# Power_Management.net
KiCad netlist of a schematic drawn in Altium Designer
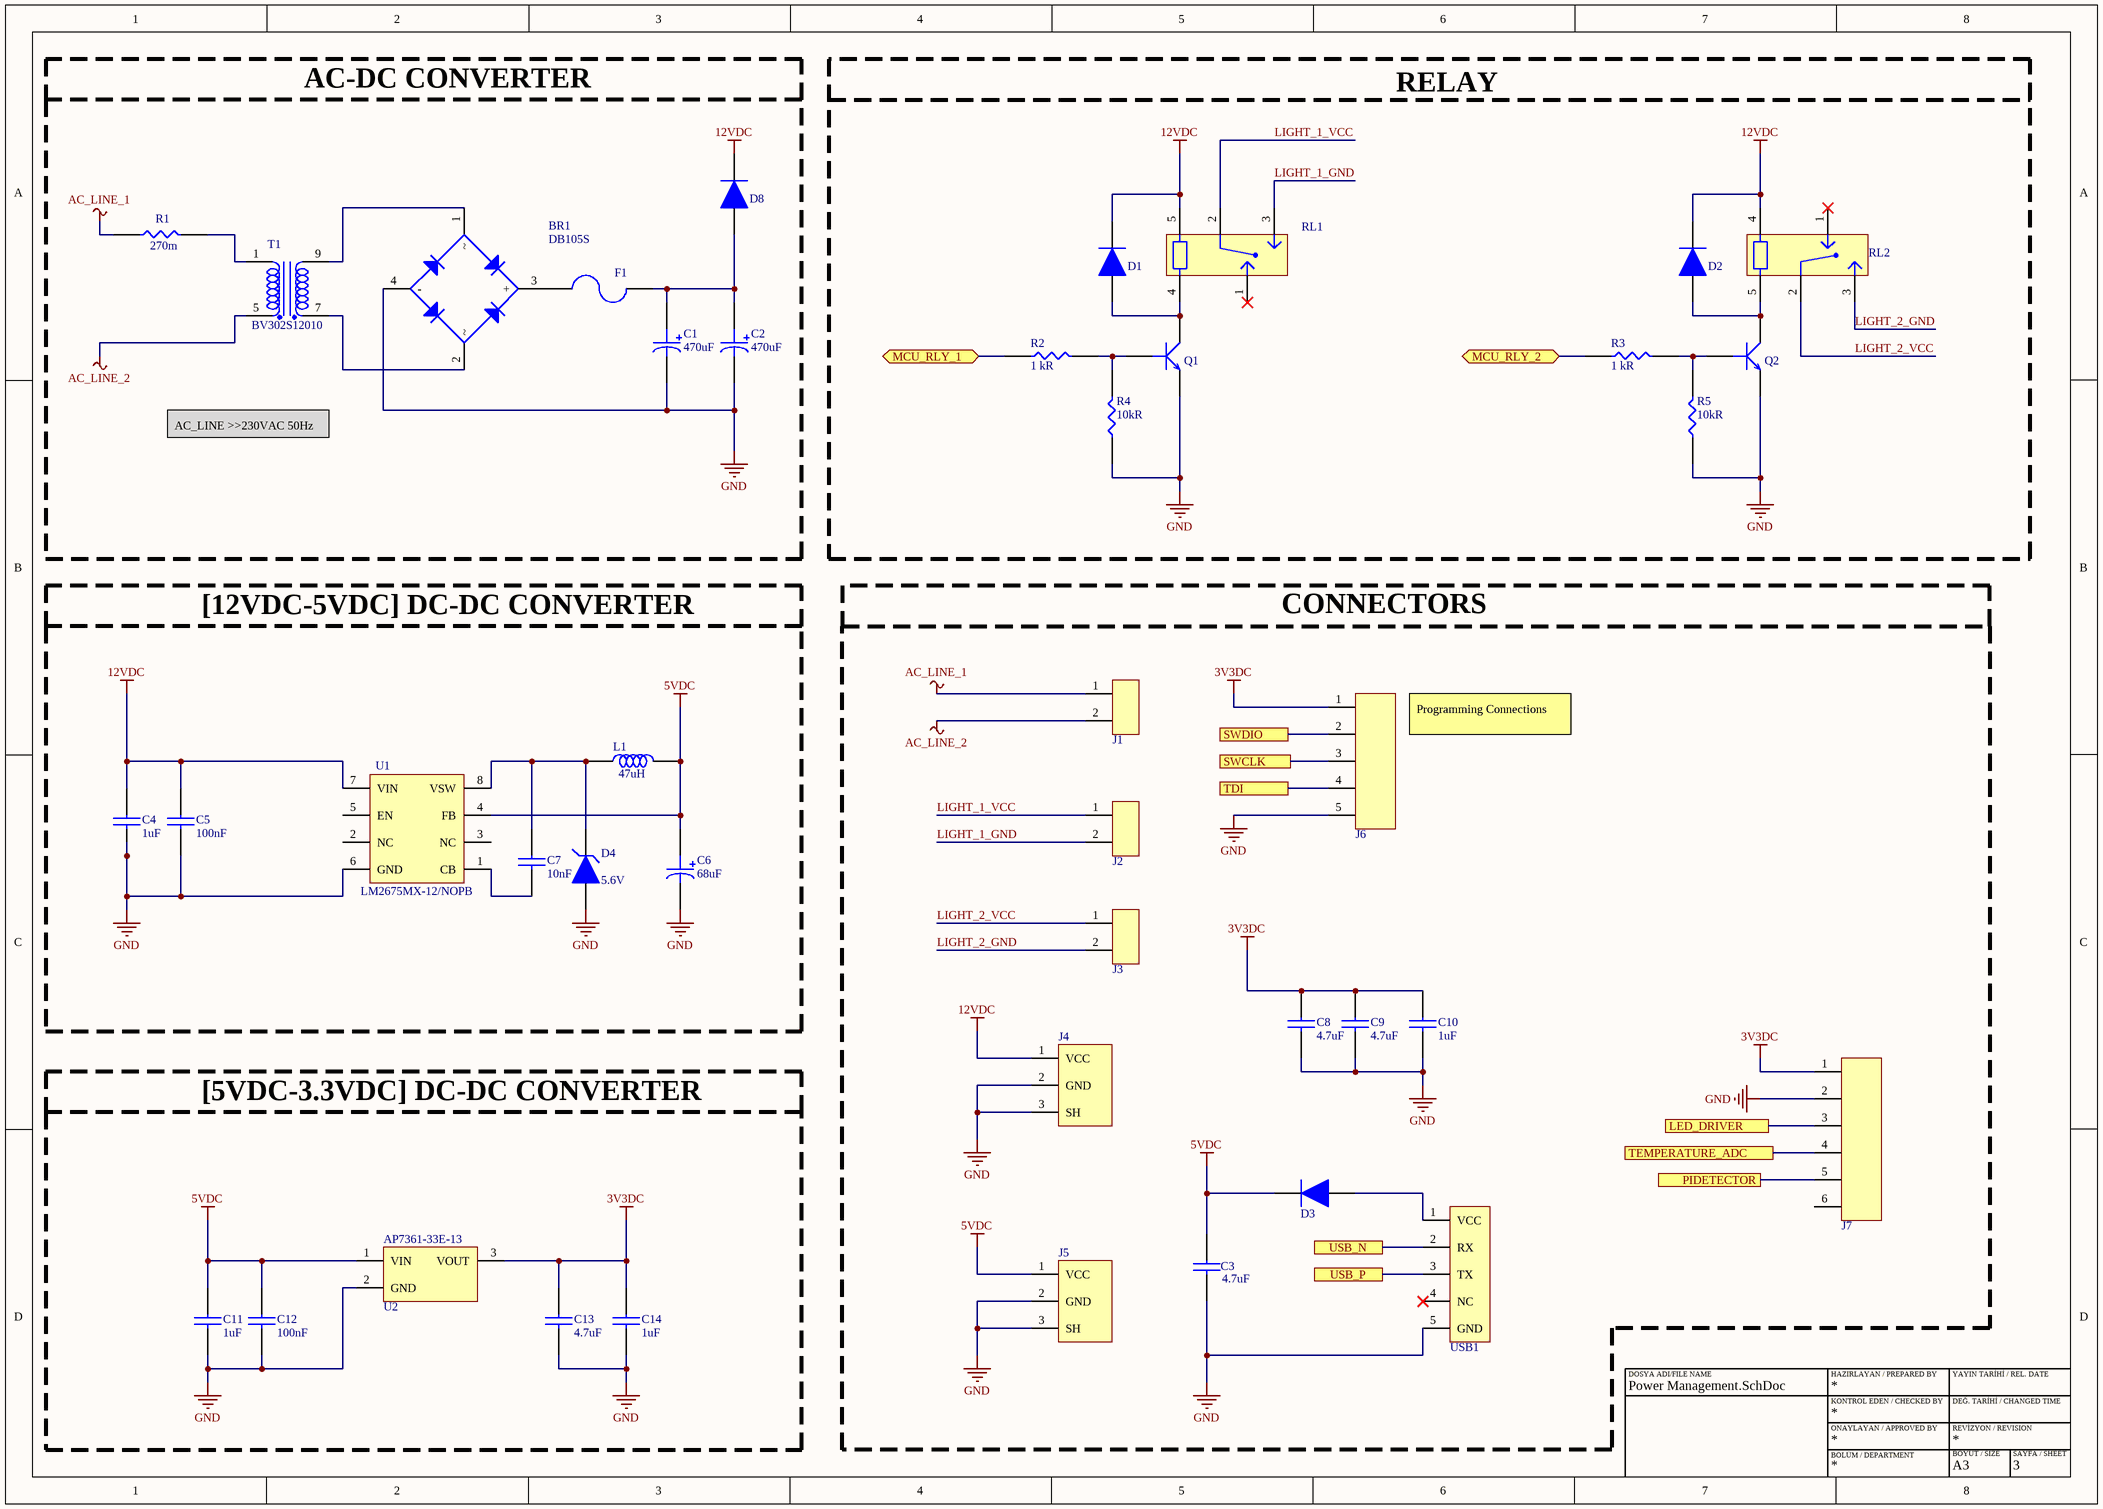
[diagram p0: Power Management.SchDoc]

(export (version "E")
  (design (tool "Eeschema 10.0.6"))
  (components
    (comp (ref "BR1")
      (value "DB105S")
      (footprint "DB105S")
      (description "Rectifier Bridge Diode Single 600V 1A 4-Pin SMD")
      (fields (field (name "MANUFACTURER") "Multicomp"))
      (libsource (lib "Integrated_Library1") (part "DB105S"))
    )
    (comp (ref "C1")
      (value "470uF")
      (footprint "CAP_RADIAL_D10_P5")
      (description "CAP ALU ELEC 470uF 50V 20%")
      (fields
        (field (name "MANUFACTURER") "KEMET")
        (field (name "MANUFACTURER PART NUMBER") "ESH477M050AH4AA")
        (field (name "DESIGNED BY") "MCP")
      )
      (libsource (lib "Integrated_Library1") (part "CAP ALU ELEC 470uF 50V"))
    )
    (comp (ref "C2")
      (value "470uF")
      (footprint "CAP_RADIAL_D10_P5")
      (description "CAP ALU ELEC 470uF 50V 20%")
      (fields
        (field (name "MANUFACTURER") "KEMET")
        (field (name "MANUFACTURER PART NUMBER") "ESH477M050AH4AA")
        (field (name "DESIGNED BY") "MCP")
      )
      (libsource (lib "Integrated_Library1") (part "CAP ALU ELEC 470uF 50V"))
    )
    (comp (ref "C3")
      (value "4.7uF")
      (footprint "CAP_0805")
      (description "CAP CER 4.7uF 10% 0805")
      (fields
        (field (name "MANUFACTURER") "Samsung")
        (field (name "MANUFACTURER PART NUMBER") "CL21A475KAQNNNE")
        (field (name "DESIGNED BY") "MCP")
      )
      (libsource (lib "Integrated_Library1") (part "CAP CER 4.7uF 0805"))
    )
    (comp (ref "C4")
      (value "1uF")
      (footprint "CAP_0805")
      (description "CAP CER 1uF 10% 0805")
      (fields
        (field (name "MANUFACTURER") "Samsung")
        (field (name "MANUFACTURER PART NUMBER") "CL21B105KBFNNNE")
        (field (name "DESIGNED BY") "MCP")
      )
      (libsource (lib "Integrated_Library1") (part "CAP CER 1uF 0805"))
    )
    (comp (ref "C5")
      (value "100nF")
      (footprint "CAP_0805")
      (description "CAP CER 100nF 10% 0805")
      (fields
        (field (name "MANUFACTURER") "Samsung")
        (field (name "MANUFACTURER PART NUMBER") "CL21B104KBCNNNC")
        (field (name "DESIGNED BY") "MCP")
      )
      (libsource (lib "Integrated_Library1") (part "CAP CER 100nF 0805"))
    )
    (comp (ref "C6")
      (value "68uF")
      (footprint "CAP_EEVSERIES")
      (description "CAP ALU 68uF 20%")
      (fields
        (field (name "MANUFACTURER") "KEMET")
        (field (name "MANUFACTURER PART NUMBER") "EEV686M035A9HAA")
        (field (name "DESIGNED BY") "MCP")
      )
      (libsource (lib "Integrated_Library1") (part "CAP ALU 68uF"))
    )
    (comp (ref "C7")
      (value "10nF")
      (footprint "CAP_0603")
      (description "CAP CER 10nF 10% 0603")
      (fields
        (field (name "MANUFACTURER") "Walsin Technologies")
        (field (name "MANUFACTURER PART NUMBER") "0603B103K160CT")
        (field (name "DESIGNED BY") "MCP")
      )
      (libsource (lib "Integrated_Library1") (part "CAP CER 10nF 0603"))
    )
    (comp (ref "C8")
      (value "4.7uF")
      (footprint "CAP_0805")
      (description "CAP CER 4.7uF 10% 0805")
      (fields
        (field (name "MANUFACTURER") "Samsung")
        (field (name "MANUFACTURER PART NUMBER") "CL21A475KAQNNNE")
        (field (name "DESIGNED BY") "MCP")
      )
      (libsource (lib "Integrated_Library1") (part "CAP CER 4.7uF 0805"))
    )
    (comp (ref "C9")
      (value "4.7uF")
      (footprint "CAP_0805")
      (description "CAP CER 4.7uF 10% 0805")
      (fields
        (field (name "MANUFACTURER") "Samsung")
        (field (name "MANUFACTURER PART NUMBER") "CL21A475KAQNNNE")
        (field (name "DESIGNED BY") "MCP")
      )
      (libsource (lib "Integrated_Library1") (part "CAP CER 4.7uF 0805"))
    )
    (comp (ref "C10")
      (value "1uF")
      (footprint "CAP_0805")
      (description "CAP CER 1uF 10% 0805")
      (fields
        (field (name "MANUFACTURER") "Samsung")
        (field (name "MANUFACTURER PART NUMBER") "CL21B105KBFNNNE")
        (field (name "DESIGNED BY") "MCP")
      )
      (libsource (lib "Integrated_Library1") (part "CAP CER 1uF 0805"))
    )
    (comp (ref "C11")
      (value "1uF")
      (footprint "CAP_0805")
      (description "CAP CER 1uF 10% 0805")
      (fields
        (field (name "MANUFACTURER") "Samsung")
        (field (name "MANUFACTURER PART NUMBER") "CL21B105KBFNNNE")
        (field (name "DESIGNED BY") "MCP")
      )
      (libsource (lib "Integrated_Library1") (part "CAP CER 1uF 0805"))
    )
    (comp (ref "C12")
      (value "100nF")
      (footprint "CAP_0603")
      (description "CAP CER 100nF 10% 0603")
      (fields
        (field (name "MANUFACTURER") "KEMET")
        (field (name "MANUFACTURER PART NUMBER") "C0603C104K5RACTU")
        (field (name "DESIGNED BY") "MCP")
      )
      (libsource (lib "Integrated_Library1") (part "CAP CER 100nF 0603"))
    )
    (comp (ref "C13")
      (value "4.7uF")
      (footprint "CAP_0805")
      (description "CAP CER 4.7uF 10% 0805")
      (fields
        (field (name "MANUFACTURER") "Samsung")
        (field (name "MANUFACTURER PART NUMBER") "CL21A475KAQNNNE")
        (field (name "DESIGNED BY") "MCP")
      )
      (libsource (lib "Integrated_Library1") (part "CAP CER 4.7uF 0805"))
    )
    (comp (ref "C14")
      (value "1uF")
      (footprint "CAP_0805")
      (description "CAP CER 1uF 10% 0805")
      (fields
        (field (name "MANUFACTURER") "Samsung")
        (field (name "MANUFACTURER PART NUMBER") "CL21B105KBFNNNE")
        (field (name "DESIGNED BY") "MCP")
      )
      (libsource (lib "Integrated_Library1") (part "CAP CER 1uF 0805"))
    )
    (comp (ref "D1")
      (value "1N4148WS")
      (footprint "SOD323F")
      (description "Diode,150mA, 75V V")
      (fields (field (name "MANUFACTURER") "onsemi") (field (name "DESIGNED BY") "MCP"))
      (libsource (lib "Integrated_Library1") (part "1N4148WS"))
    )
    (comp (ref "D2")
      (value "1N4148WS")
      (footprint "SOD323F")
      (description "Diode,150mA, 75V V")
      (fields (field (name "MANUFACTURER") "onsemi") (field (name "DESIGNED BY") "MCP"))
      (libsource (lib "Integrated_Library1") (part "1N4148WS"))
    )
    (comp (ref "D3")
      (value "1N4148WS")
      (footprint "SOD323F")
      (description "Diode,150mA, 75V V")
      (fields (field (name "MANUFACTURER") "onsemi") (field (name "DESIGNED BY") "MCP"))
      (libsource (lib "Integrated_Library1") (part "1N4148WS"))
    )
    (comp (ref "D4")
      (value "1SMB5919BT3G")
      (footprint "SMB")
      (description "Zener Diode, 5.6V V(Z), 5%, 0.55W, Silicon, Unidirectional, DO-214AA")
      (fields
        (field (name "MANUFACTURER") "onsemi")
        (field (name "REFERENCE VOLTAGE-NOM") "5.6V")
        (field (name "DESIGNED BY") "MCP")
      )
      (libsource (lib "Integrated_Library1") (part "1SMB5919BT3G"))
    )
    (comp (ref "D8")
      (value "1N4148WS")
      (footprint "SOD323F")
      (description "Diode,150mA, 75V V")
      (fields (field (name "MANUFACTURER") "onsemi") (field (name "DESIGNED BY") "MCP"))
      (libsource (lib "Integrated_Library1") (part "1N4148WS"))
    )
    (comp (ref "F1")
      (value "3413.0216.22")
      (footprint "FUSE 3413.0216.22")
      (description "Electric Fuse, Very Fast Blow, 1A, 32VAC, 63VDC, 63A (IR), Surface Mount, 1206")
      (fields (field (name "MANUFACTURER") "Schurter") (field (name "DESIGNED BY") "MCP"))
      (libsource (lib "Integrated_Library1") (part "FUSE 3413.0216.22"))
    )
    (comp (ref "J1")
      (value "TBP01R1-508-02BE")
      (footprint "TBP01R1-508")
      (description "Strip Terminal Block")
      (fields (field (name "MANUFACTURER") "Same Sky") (field (name "DESIGNED BY") "MCP"))
      (libsource (lib "Integrated_Library1") (part "TBP01R1-508-02BE"))
    )
    (comp (ref "J2")
      (value "TBP01R1-508-02BE")
      (footprint "TBP01R1-508")
      (description "Strip Terminal Block")
      (fields (field (name "MANUFACTURER") "Same Sky") (field (name "DESIGNED BY") "MCP"))
      (libsource (lib "Integrated_Library1") (part "TBP01R1-508-02BE"))
    )
    (comp (ref "J3")
      (value "TBP01R1-508-02BE")
      (footprint "TBP01R1-508")
      (description "Strip Terminal Block")
      (fields (field (name "MANUFACTURER") "Same Sky") (field (name "DESIGNED BY") "MCP"))
      (libsource (lib "Integrated_Library1") (part "TBP01R1-508-02BE"))
    )
    (comp (ref "J4")
      (value "PJ-037AH-SMT-TR")
      (footprint "JACK")
      (description "DC Power Connectors Power Jacks")
      (fields (field (name "DESIGNED BY") "MCP"))
      (libsource (lib "Integrated_Library1") (part "PJ-037AH-SMT-TR"))
    )
    (comp (ref "J5")
      (value "PJ-037AH-SMT-TR")
      (footprint "JACK")
      (description "DC Power Connectors Power Jacks")
      (fields (field (name "DESIGNED BY") "MCP"))
      (libsource (lib "Integrated_Library1") (part "PJ-037AH-SMT-TR"))
    )
    (comp (ref "J6")
      (value "SMH-105-02-L-S")
      (footprint "PIN_HEADER1X5_RA")
      (fields (field (name "MANUFACTURER") "Samtec") (field (name "DESIGNED BY") "MCP"))
      (libsource (lib "Integrated_Library1") (part "SMH-105-02-L-S"))
    )
    (comp (ref "J7")
      (value "64800611622_CONN_6PIN")
      (footprint "64800611622_CONN_6PIN")
      (description "1.50 mm 6 pin connector")
      (fields
        (field (name "MANUFACTURER") "Wurth Electronics")
        (field (name "MANUFACTURER PART NUMBER") "64800611622")
      )
      (libsource (lib "Integrated_Library1") (part "64800611622_CONN_6PIN"))
    )
    (comp (ref "L1")
      (value "47uH")
      (footprint "IND_1212")
      (description "FIXED IND 47UH 390MA 2.3OHM SMD")
      (fields
        (field (name "MANUFACTURER") "Wurth Electronics")
        (field (name "MANUFACTURER PART NUMBER") "78438335470")
        (field (name "DESIGNED BY") "MCP")
      )
      (libsource (lib "Integrated_Library1") (part "IND 47uH"))
    )
    (comp (ref "Q1")
      (value "MMBT3904.7.F")
      (footprint "SOT-23F")
      (description "Small Signal Bipolar Transistor, 0.2A I(C), 40V V(BR)CEO, 1-Element, NPN, Silicon")
      (fields
        (field (name "MANUFACTURER") "Diodes Zetex")
        (field (name "MANUFACTURER PART NUMBER") "MMBT3904-7-F")
        (field (name "DESIGNED BY") "MCP")
      )
      (libsource (lib "Integrated_Library1") (part "MMBT3904.7.F"))
    )
    (comp (ref "Q2")
      (value "MMBT3904.7.F")
      (footprint "SOT-23F")
      (description "Small Signal Bipolar Transistor, 0.2A I(C), 40V V(BR)CEO, 1-Element, NPN, Silicon")
      (fields
        (field (name "MANUFACTURER") "Diodes Zetex")
        (field (name "MANUFACTURER PART NUMBER") "MMBT3904-7-F")
        (field (name "DESIGNED BY") "MCP")
      )
      (libsource (lib "Integrated_Library1") (part "MMBT3904.7.F"))
    )
    (comp (ref "R1")
      (value "270m")
      (footprint "RES_AXIAL_W")
      (description "Fixed Resistor, Wire Wound, 5W, 0.27ohm, 200V, 5% +/-Tol, 300ppm/Cel, 8738")
      (fields
        (field (name "MANUFACTURER") "NTE Electronics")
        (field (name "MANUFACTURER PART NUMBER") "5WD27")
        (field (name "DESIGNED BY") "MCP")
      )
      (libsource (lib "Integrated_Library1") (part "5WD27"))
    )
    (comp (ref "R2")
      (value "1 kR")
      (footprint "RES_0603")
      (fields
        (field (name "MANUFACTURER") "Stackpole Electronics")
        (field (name "MANUFACTURER PART NUMBER") "RMCF0603FT1K00")
        (field (name "TOLERANCE") "1%")
      )
      (libsource (lib "Integrated_Library1") (part "RES 1K OHM 0603"))
    )
    (comp (ref "R3")
      (value "1 kR")
      (footprint "RES_0603")
      (fields
        (field (name "MANUFACTURER") "Stackpole Electronics")
        (field (name "MANUFACTURER PART NUMBER") "RMCF0603FT1K00")
        (field (name "TOLERANCE") "1%")
      )
      (libsource (lib "Integrated_Library1") (part "RES 1K OHM 0603"))
    )
    (comp (ref "R4")
      (value "10kR")
      (footprint "RES_0603")
      (fields
        (field (name "MANUFACTURER") "Yageo")
        (field (name "MANUFACTURER PART NUMBER") "RC0603FR-0710KL")
        (field (name "TOLERANCE") "1%")
        (field (name "DESIGNED BY") "MCP")
      )
      (libsource (lib "Integrated_Library1") (part "RES 10K OHM 0603"))
    )
    (comp (ref "R5")
      (value "10kR")
      (footprint "RES_0603")
      (fields
        (field (name "MANUFACTURER") "Yageo")
        (field (name "MANUFACTURER PART NUMBER") "RC0603FR-0710KL")
        (field (name "TOLERANCE") "1%")
        (field (name "DESIGNED BY") "MCP")
      )
      (libsource (lib "Integrated_Library1") (part "RES 10K OHM 0603"))
    )
    (comp (ref "RL1")
      (value "ALQ112")
      (footprint "ALQ112")
      (fields (field (name "MANUFACTURER") "Panasonic"))
      (libsource (lib "") (part "ALQ112_1"))
    )
    (comp (ref "RL2")
      (value "ALQ112")
      (footprint "ALQ112")
      (fields (field (name "MANUFACTURER") "Panasonic"))
      (libsource (lib "Integrated_Library1") (part "ALQ112"))
    )
    (comp (ref "T1")
      (value "BV302S12010")
      (footprint "BV302S")
      (description "Split Bobbin Power Transformer, 1VA")
      (fields (field (name "MANUFACTURER") "Zettler Magnetics") (field (name "DESIGNED BY") "MCP"))
      (libsource (lib "Integrated_Library1") (part "BV302S12010"))
    )
    (comp (ref "U1")
      (value "LM2675MX-12/NOPB")
      (footprint "SOIC-8")
      (description "Switching Regulator, Voltage-mode, 2.2A, 275kHz Switching Freq-Max, DMOS, PDSO8")
      (fields (field (name "MANUFACTURER") "TI National Semiconductor") (field (name "DESIGNED BY") "MCP"))
      (libsource (lib "Integrated_Library1") (part "LM2675MX-12/NOPB"))
    )
    (comp (ref "U2")
      (value "AP7361-33E-13")
      (footprint "SOT-223")
      (description "Fixed Positive LDO Regulator, 3.3V, 0.7V Dropout, CMOS, PSSO3")
      (fields (field (name "MANUFACTURER") "Diodes") (field (name "DESIGNED BY") "MCP"))
      (libsource (lib "Integrated_Library1") (part "AP7361-33E-13"))
    )
    (comp (ref "USB1")
      (value "10118192.0001LF")
      (footprint "MICRO_B_USB")
      (description "CONN USB MICRO B RECPT SMT R/A")
      (fields
        (field (name "MANUFACTURER") "Amphenol ICC / FCI")
        (field (name "MANUFACTURER PART NUMBER") "10118192-0001LF")
        (field (name "DESIGNED BY") "MCP")
      )
      (libsource (lib "Integrated_Library1") (part "Micro B USB Connector"))
    )
  )
  (nets
    (net (code "1") (name "/LED_DRIVER") (class "Default") (node (ref "J7") (pin "3") (pintype "passive")))
    (net (code "2") (name "/LIGHT_1_GND") (class "Default")
      (node (ref "J2") (pin "2") (pinfunction "2_2") (pintype "passive"))
      (node (ref "RL1") (pin "3") (pinfunction "3_3") (pintype "passive"))
    )
    (net (code "3") (name "/LIGHT_1_VCC") (class "Default")
      (node (ref "J2") (pin "1") (pinfunction "1_1") (pintype "power_in"))
      (node (ref "RL1") (pin "2") (pinfunction "2_2") (pintype "passive"))
    )
    (net (code "4") (name "/LIGHT_2_GND") (class "Default")
      (node (ref "J3") (pin "2") (pinfunction "2_2") (pintype "passive"))
      (node (ref "RL2") (pin "3") (pinfunction "3_3") (pintype "passive"))
    )
    (net (code "5") (name "/LIGHT_2_VCC") (class "Default")
      (node (ref "J3") (pin "1") (pinfunction "1_1") (pintype "power_in"))
      (node (ref "RL2") (pin "2") (pinfunction "2_2") (pintype "passive"))
    )
    (net (code "6") (name "/MCU_RLY_1") (class "Default")
      (node (ref "R2") (pin "1") (pinfunction "1_1") (pintype "passive"))
    )
    (net (code "7") (name "/MCU_RLY_2") (class "Default")
      (node (ref "R3") (pin "1") (pinfunction "1_1") (pintype "passive"))
    )
    (net (code "8") (name "/PIDETECTOR") (class "Default") (node (ref "J7") (pin "5") (pintype "passive")))
    (net (code "9") (name "/SWCLK") (class "Default")
      (node (ref "J6") (pin "3") (pinfunction "3_3") (pintype "passive"))
    )
    (net (code "10") (name "/SWDIO") (class "Default")
      (node (ref "J6") (pin "2") (pinfunction "2_2") (pintype "passive"))
    )
    (net (code "11") (name "/TDI") (class "Default")
      (node (ref "J6") (pin "4") (pinfunction "4_4") (pintype "passive"))
    )
    (net (code "12") (name "/TEMPERATURE_ADC") (class "Default")
      (node (ref "J7") (pin "4") (pintype "passive"))
    )
    (net (code "13") (name "/USB_N") (class "Default")
      (node (ref "USB1") (pin "2") (pinfunction "RX_2") (pintype "passive"))
    )
    (net (code "14") (name "/USB_P") (class "Default")
      (node (ref "USB1") (pin "3") (pinfunction "TX_3") (pintype "passive"))
    )
    (net (code "15") (name "3V3DC") (class "Default")
      (node (ref "C10") (pin "2") (pinfunction "2_2") (pintype "passive"))
      (node (ref "C13") (pin "2") (pinfunction "2_2") (pintype "passive"))
      (node (ref "C14") (pin "2") (pinfunction "2_2") (pintype "passive"))
      (node (ref "C8") (pin "2") (pinfunction "2_2") (pintype "passive"))
      (node (ref "C9") (pin "2") (pinfunction "2_2") (pintype "passive"))
      (node (ref "J6") (pin "1") (pinfunction "1_1") (pintype "passive"))
      (node (ref "J7") (pin "1") (pintype "passive"))
      (node (ref "U2") (pin "3") (pinfunction "VOUT_3") (pintype "passive"))
    )
    (net (code "16") (name "5VDC") (class "Default")
      (node (ref "C11") (pin "2") (pinfunction "2_2") (pintype "passive"))
      (node (ref "C12") (pin "2") (pinfunction "2_2") (pintype "passive"))
      (node (ref "C3") (pin "2") (pinfunction "2_2") (pintype "passive"))
      (node (ref "C6") (pin "1") (pinfunction "1_1") (pintype "passive"))
      (node (ref "D3") (pin "1") (pinfunction "1_1") (pintype "passive"))
      (node (ref "J5") (pin "1") (pinfunction "VCC_1") (pintype "power_in"))
      (node (ref "L1") (pin "2") (pinfunction "2_2") (pintype "passive"))
      (node (ref "U1") (pin "4") (pinfunction "FB_4") (pintype "passive"))
      (node (ref "U2") (pin "1") (pinfunction "VIN_1") (pintype "passive"))
    )
    (net (code "17") (name "12VDC") (class "Default")
      (node (ref "C4") (pin "2") (pinfunction "2_2") (pintype "passive"))
      (node (ref "C5") (pin "2") (pinfunction "2_2") (pintype "passive"))
      (node (ref "D1") (pin "1") (pinfunction "1_1") (pintype "passive"))
      (node (ref "D2") (pin "1") (pinfunction "1_1") (pintype "passive"))
      (node (ref "D8") (pin "1") (pinfunction "1_1") (pintype "passive"))
      (node (ref "J4") (pin "1") (pinfunction "VCC_1") (pintype "power_in"))
      (node (ref "RL1") (pin "5") (pinfunction "5_5") (pintype "passive"))
      (node (ref "RL2") (pin "4") (pinfunction "4_4") (pintype "passive"))
      (node (ref "U1") (pin "7") (pinfunction "VIN_7") (pintype "passive"))
    )
    (net (code "18") (name "AC_LINE_1") (class "Default")
      (node (ref "J1") (pin "1") (pinfunction "1_1") (pintype "power_in"))
      (node (ref "R1") (pin "1") (pinfunction "1_1") (pintype "passive"))
    )
    (net (code "19") (name "AC_LINE_2") (class "Default")
      (node (ref "J1") (pin "2") (pinfunction "2_2") (pintype "passive"))
      (node (ref "T1") (pin "5") (pinfunction "5_5") (pintype "passive"))
    )
    (net (code "20") (name "GND") (class "Default")
      (node (ref "BR1") (pin "4") (pinfunction "-_4") (pintype "passive"))
      (node (ref "C1") (pin "2") (pinfunction "2_2") (pintype "passive"))
      (node (ref "C10") (pin "1") (pinfunction "1_1") (pintype "passive"))
      (node (ref "C11") (pin "1") (pinfunction "1_1") (pintype "passive"))
      (node (ref "C12") (pin "1") (pinfunction "1_1") (pintype "passive"))
      (node (ref "C13") (pin "1") (pinfunction "1_1") (pintype "passive"))
      (node (ref "C14") (pin "1") (pinfunction "1_1") (pintype "passive"))
      (node (ref "C2") (pin "2") (pinfunction "2_2") (pintype "passive"))
      (node (ref "C3") (pin "1") (pinfunction "1_1") (pintype "passive"))
      (node (ref "C4") (pin "1") (pinfunction "1_1") (pintype "passive"))
      (node (ref "C5") (pin "1") (pinfunction "1_1") (pintype "passive"))
      (node (ref "C6") (pin "2") (pinfunction "2_2") (pintype "passive"))
      (node (ref "C8") (pin "1") (pinfunction "1_1") (pintype "passive"))
      (node (ref "C9") (pin "1") (pinfunction "1_1") (pintype "passive"))
      (node (ref "D4") (pin "A") (pinfunction "A_A") (pintype "passive"))
      (node (ref "J4") (pin "2") (pinfunction "GND_2") (pintype "power_in"))
      (node (ref "J4") (pin "3") (pinfunction "SH_3") (pintype "power_in"))
      (node (ref "J5") (pin "2") (pinfunction "GND_2") (pintype "power_in"))
      (node (ref "J5") (pin "3") (pinfunction "SH_3") (pintype "power_in"))
      (node (ref "J6") (pin "5") (pinfunction "5_5") (pintype "passive"))
      (node (ref "J7") (pin "2") (pintype "passive"))
      (node (ref "Q1") (pin "2") (pinfunction "E_2") (pintype "passive"))
      (node (ref "Q2") (pin "2") (pinfunction "E_2") (pintype "passive"))
      (node (ref "R4") (pin "1") (pinfunction "1_1") (pintype "passive"))
      (node (ref "R5") (pin "1") (pinfunction "1_1") (pintype "passive"))
      (node (ref "U1") (pin "6") (pinfunction "GND_6") (pintype "passive"))
      (node (ref "U2") (pin "2") (pinfunction "GND_2") (pintype "passive"))
      (node (ref "USB1") (pin "5") (pinfunction "GND_5") (pintype "passive"))
    )
    (net (code "21") (name "Net-(BR1-+)") (class "Default")
      (node (ref "BR1") (pin "3") (pinfunction "+_3") (pintype "passive"))
      (node (ref "F1") (pin "1") (pinfunction "1_1") (pintype "passive"))
    )
    (net (code "22") (name "Net-(BR1-~-Pad1)") (class "Default")
      (node (ref "BR1") (pin "1") (pinfunction "~_1") (pintype "passive"))
      (node (ref "T1") (pin "9") (pinfunction "9_9") (pintype "passive"))
    )
    (net (code "23") (name "Net-(BR1-~-Pad2)") (class "Default")
      (node (ref "BR1") (pin "2") (pinfunction "~_2") (pintype "passive"))
      (node (ref "T1") (pin "7") (pinfunction "7_7") (pintype "passive"))
    )
    (net (code "24") (name "Net-(C1-Pad1)") (class "Default")
      (node (ref "C1") (pin "1") (pinfunction "1_1") (pintype "passive"))
      (node (ref "C2") (pin "1") (pinfunction "1_1") (pintype "passive"))
      (node (ref "D8") (pin "2") (pinfunction "2_2") (pintype "passive"))
      (node (ref "F1") (pin "2") (pinfunction "2_2") (pintype "passive"))
    )
    (net (code "25") (name "Net-(Q1-B)") (class "Default")
      (node (ref "Q1") (pin "1") (pinfunction "B_1") (pintype "passive"))
      (node (ref "R2") (pin "2") (pinfunction "2_2") (pintype "passive"))
      (node (ref "R4") (pin "2") (pinfunction "2_2") (pintype "passive"))
    )
    (net (code "26") (name "Net-(Q1-C)") (class "Default")
      (node (ref "D1") (pin "2") (pinfunction "2_2") (pintype "passive"))
      (node (ref "Q1") (pin "3") (pinfunction "C_3") (pintype "passive"))
      (node (ref "RL1") (pin "4") (pinfunction "4_4") (pintype "passive"))
    )
    (net (code "27") (name "Net-(Q2-B)") (class "Default")
      (node (ref "Q2") (pin "1") (pinfunction "B_1") (pintype "passive"))
      (node (ref "R3") (pin "2") (pinfunction "2_2") (pintype "passive"))
      (node (ref "R5") (pin "2") (pinfunction "2_2") (pintype "passive"))
    )
    (net (code "28") (name "Net-(Q2-C)") (class "Default")
      (node (ref "D2") (pin "2") (pinfunction "2_2") (pintype "passive"))
      (node (ref "Q2") (pin "3") (pinfunction "C_3") (pintype "passive"))
      (node (ref "RL2") (pin "5") (pinfunction "5_5") (pintype "passive"))
    )
    (net (code "29") (name "Net-(R1-Pad2)") (class "Default")
      (node (ref "R1") (pin "2") (pinfunction "2_2") (pintype "passive"))
      (node (ref "T1") (pin "1") (pinfunction "1_1") (pintype "passive"))
    )
    (net (code "30") (name "Net-(U1-CB)") (class "Default")
      (node (ref "C7") (pin "1") (pinfunction "1_1") (pintype "passive"))
      (node (ref "U1") (pin "1") (pinfunction "CB_1") (pintype "passive"))
    )
    (net (code "31") (name "Net-(U1-VSW)") (class "Default")
      (node (ref "C7") (pin "2") (pinfunction "2_2") (pintype "passive"))
      (node (ref "D4") (pin "C") (pinfunction "C_C") (pintype "passive"))
      (node (ref "L1") (pin "1") (pinfunction "1_1") (pintype "passive"))
      (node (ref "U1") (pin "8") (pinfunction "VSW_8") (pintype "passive"))
    )
    (net (code "32") (name "Net-(USB1-VCC)") (class "Default")
      (node (ref "D3") (pin "2") (pinfunction "2_2") (pintype "passive"))
      (node (ref "USB1") (pin "1") (pinfunction "VCC_1") (pintype "passive"))
    )
    (net (code "33") (name "unconnected-(J7-Pad6)") (class "Default")
      (node (ref "J7") (pin "6") (pintype "passive"))
    )
    (net (code "34") (name "unconnected-(RL1-Pad1)") (class "Default")
      (node (ref "RL1") (pin "1") (pinfunction "1_1") (pintype "passive+no_connect"))
    )
    (net (code "35") (name "unconnected-(RL2-Pad1)") (class "Default")
      (node (ref "RL2") (pin "1") (pinfunction "1_1") (pintype "passive+no_connect"))
    )
    (net (code "36") (name "unconnected-(U1-EN-Pad5)") (class "Default")
      (node (ref "U1") (pin "5") (pinfunction "EN_5") (pintype "passive"))
    )
    (net (code "37") (name "unconnected-(U1-NC-Pad2)") (class "Default")
      (node (ref "U1") (pin "2") (pinfunction "NC_2") (pintype "passive"))
    )
    (net (code "38") (name "unconnected-(U1-NC-Pad3)") (class "Default")
      (node (ref "U1") (pin "3") (pinfunction "NC_3") (pintype "passive"))
    )
    (net (code "39") (name "unconnected-(USB1-NC-Pad4)") (class "Default")
      (node (ref "USB1") (pin "4") (pinfunction "NC_4") (pintype "passive+no_connect"))
    )
  )
)
